# controller_board.net
KiCad netlist of a schematic drawn in EAGLE
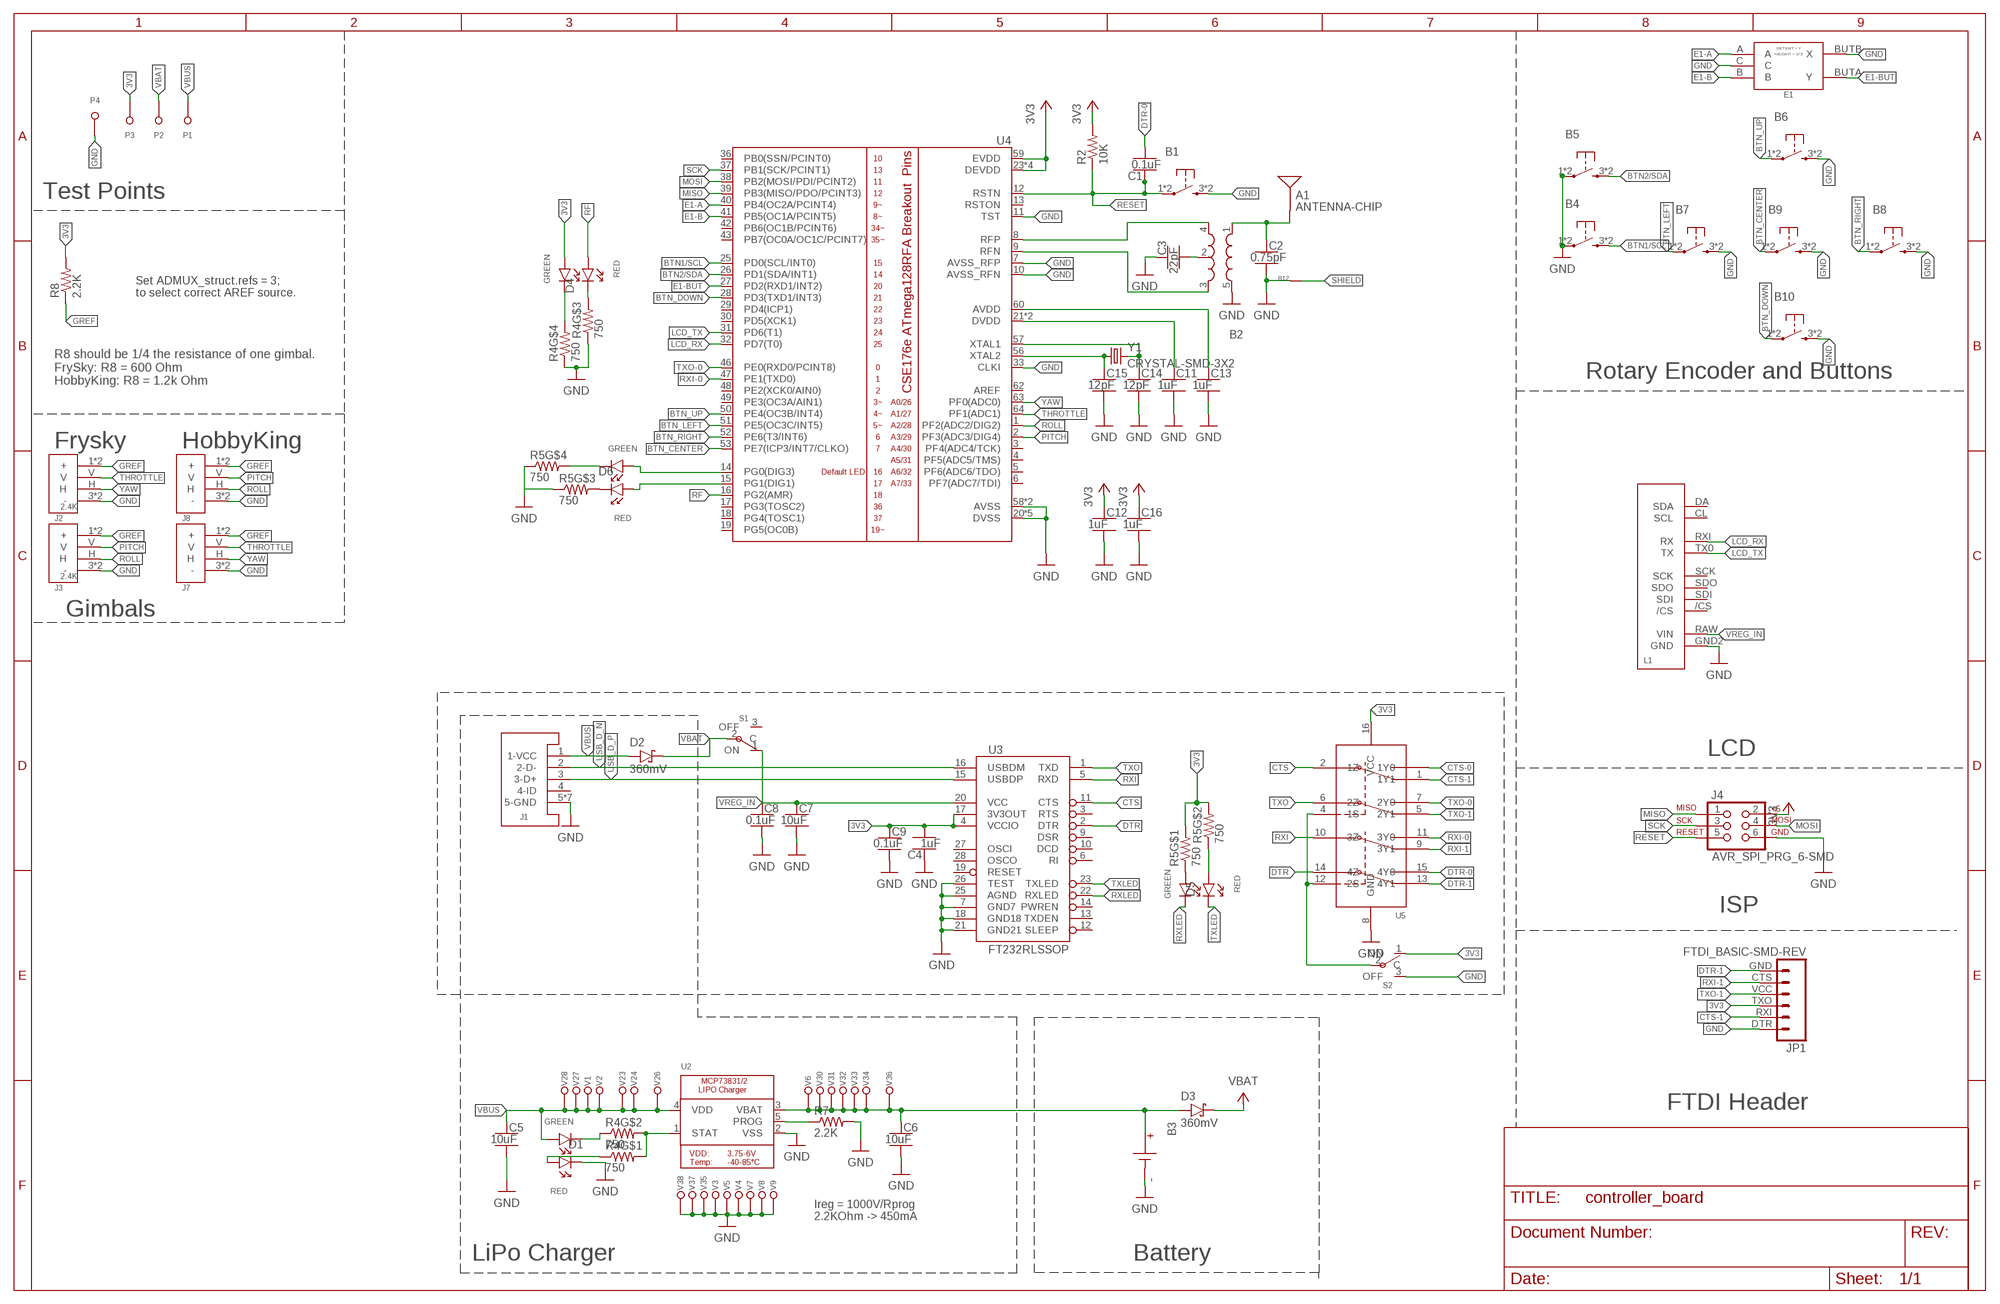
[diagram p0: schematic, sheet 1]

(export (version "E")
  (design (tool "Eeschema 10.0.6"))
  (components
    (comp (ref "A1")
      (value "ANTENNA-CHIP")
      (footprint "eagle-import:ANTENNA-CHIP")
      (fields
        (field (name "MFR") "Linx Technologies Inc.")
        (field (name "MPN") "ANT-2.45-CHP-T")
        (field (name "CREATOR") "Swanson")
        (field (name "REVIEWER") "Swanson")
      )
      (libsource (lib "eagle-import") (part "ANTENNA-CHIP"))
    )
    (comp (ref "B1")
      (value "PUSHBUTTON_-4.5X4.5")
      (footprint "eagle-import:4.5MM_TACTILE_SWITCH_TL3305AF160QG")
      (fields (field (name "CREATOR") "Swanson"))
      (libsource (lib "eagle-import") (part "PUSHBUTTON_-4.5X4.5"))
    )
    (comp (ref "B2")
      (value "BALUN0805")
      (footprint "eagle-import:BALUN")
      (fields
        (field (name "MFR") "Wurth Electronics Inc")
        (field (name "MPN") "748421245")
        (field (name "CREATOR") "Swanson")
        (field (name "REVIEWER") "Swanson")
      )
      (libsource (lib "eagle-import") (part "BALUN0805"))
    )
    (comp (ref "B3")
      (value "BATTERY")
      (footprint "eagle-import:BATTERY-TERMINALS")
      (fields (field (name "CREATOR") "Swanson"))
      (libsource (lib "eagle-import") (part "BATTERY"))
    )
    (comp (ref "B4")
      (value "PUSHBUTTON_-4.5X4.5")
      (footprint "eagle-import:4.5MM_TACTILE_SWITCH_TL3305AF160QG")
      (fields (field (name "CREATOR") "Swanson"))
      (libsource (lib "eagle-import") (part "PUSHBUTTON_-4.5X4.5"))
    )
    (comp (ref "B5")
      (value "PUSHBUTTON_-4.5X4.5")
      (footprint "eagle-import:4.5MM_TACTILE_SWITCH_TL3305AF160QG")
      (fields (field (name "CREATOR") "Swanson"))
      (libsource (lib "eagle-import") (part "PUSHBUTTON_-4.5X4.5"))
    )
    (comp (ref "B6")
      (value "PUSHBUTTON_-4.5X4.5")
      (footprint "eagle-import:4.5MM_TACTILE_SWITCH_TL3305AF160QG")
      (fields (field (name "CREATOR") "Swanson"))
      (libsource (lib "eagle-import") (part "PUSHBUTTON_-4.5X4.5"))
    )
    (comp (ref "B7")
      (value "PUSHBUTTON_-4.5X4.5")
      (footprint "eagle-import:4.5MM_TACTILE_SWITCH_TL3305AF160QG")
      (fields (field (name "CREATOR") "Swanson"))
      (libsource (lib "eagle-import") (part "PUSHBUTTON_-4.5X4.5"))
    )
    (comp (ref "B8")
      (value "PUSHBUTTON_-4.5X4.5")
      (footprint "eagle-import:4.5MM_TACTILE_SWITCH_TL3305AF160QG")
      (fields (field (name "CREATOR") "Swanson"))
      (libsource (lib "eagle-import") (part "PUSHBUTTON_-4.5X4.5"))
    )
    (comp (ref "B9")
      (value "PUSHBUTTON_-4.5X4.5")
      (footprint "eagle-import:4.5MM_TACTILE_SWITCH_TL3305AF160QG")
      (fields (field (name "CREATOR") "Swanson"))
      (libsource (lib "eagle-import") (part "PUSHBUTTON_-4.5X4.5"))
    )
    (comp (ref "B10")
      (value "PUSHBUTTON_-4.5X4.5")
      (footprint "eagle-import:4.5MM_TACTILE_SWITCH_TL3305AF160QG")
      (fields (field (name "CREATOR") "Swanson"))
      (libsource (lib "eagle-import") (part "PUSHBUTTON_-4.5X4.5"))
    )
    (comp (ref "B12")
      (value "NET_BRIDGE")
      (footprint "eagle-import:NET_BRIDGE")
      (fields (field (name "CREATOR") "Michael Gonzalez"))
      (libsource (lib "eagle-import") (part "NET_BRIDGE"))
    )
    (comp (ref "C1")
      (value "0.1uF")
      (footprint "eagle-import:CAPC1608X100")
      (fields (field (name "CREATOR") "Swanson"))
      (libsource (lib "eagle-import") (part "CAPACITOR-NP_SMD-0603_CERAMIC-0.1UF"))
    )
    (comp (ref "C2")
      (value "0.75pF")
      (footprint "eagle-import:CAPC1608X100")
      (fields (field (name "CREATOR") "Swanson"))
      (libsource (lib "eagle-import") (part "CAPACITOR-NP_SMD-0603_CERAMIC-0.75PF"))
    )
    (comp (ref "C3")
      (value "22pF")
      (footprint "eagle-import:CAPC1608X100")
      (fields (field (name "CREATOR") "Swanson"))
      (libsource (lib "eagle-import") (part "CAPACITOR-NP_SMD-0603_CERAMIC-22PF"))
    )
    (comp (ref "C4")
      (value "1uF")
      (footprint "eagle-import:CAPC1608X100")
      (fields (field (name "CREATOR") "Swanson"))
      (libsource (lib "eagle-import") (part "CAPACITOR-NP_SMD-0603_CERAMIC-1UF"))
    )
    (comp (ref "C5")
      (value "10uF")
      (footprint "eagle-import:CAPC1608X100")
      (fields (field (name "CREATOR") "Swanson"))
      (libsource (lib "eagle-import") (part "CAPACITOR-NP_SMD-0603_CERAMIC-10UF"))
    )
    (comp (ref "C6")
      (value "10uF")
      (footprint "eagle-import:CAPC1608X100")
      (fields (field (name "CREATOR") "Swanson"))
      (libsource (lib "eagle-import") (part "CAPACITOR-NP_SMD-0603_CERAMIC-10UF"))
    )
    (comp (ref "C7")
      (value "10uF")
      (footprint "eagle-import:CAPC1608X100")
      (fields (field (name "CREATOR") "Swanson"))
      (libsource (lib "eagle-import") (part "CAPACITOR-NP_SMD-0603_CERAMIC-10UF"))
    )
    (comp (ref "C8")
      (value "0.1uF")
      (footprint "eagle-import:CAPC1608X100")
      (fields (field (name "CREATOR") "Swanson"))
      (libsource (lib "eagle-import") (part "CAPACITOR-NP_SMD-0603_CERAMIC-0.1UF"))
    )
    (comp (ref "C9")
      (value "0.1uF")
      (footprint "eagle-import:CAPC1608X100")
      (fields (field (name "CREATOR") "Swanson"))
      (libsource (lib "eagle-import") (part "CAPACITOR-NP_SMD-0603_CERAMIC-0.1UF"))
    )
    (comp (ref "C11")
      (value "1uF")
      (footprint "eagle-import:CAPC1608X100")
      (fields (field (name "CREATOR") "Swanson"))
      (libsource (lib "eagle-import") (part "CAPACITOR-NP_SMD-0603_CERAMIC-1UF"))
    )
    (comp (ref "C12")
      (value "1uF")
      (footprint "eagle-import:CAPC1608X100")
      (fields (field (name "CREATOR") "Swanson"))
      (libsource (lib "eagle-import") (part "CAPACITOR-NP_SMD-0603_CERAMIC-1UF"))
    )
    (comp (ref "C13")
      (value "1uF")
      (footprint "eagle-import:CAPC1608X100")
      (fields (field (name "CREATOR") "Swanson"))
      (libsource (lib "eagle-import") (part "CAPACITOR-NP_SMD-0603_CERAMIC-1UF"))
    )
    (comp (ref "C14")
      (value "12pF")
      (footprint "eagle-import:CAPC1608X100")
      (fields (field (name "CREATOR") "Swanson"))
      (libsource (lib "eagle-import") (part "CAPACITOR-NP_SMD-0603_CERAMIC-12PF"))
    )
    (comp (ref "C15")
      (value "12pF")
      (footprint "eagle-import:CAPC1608X100")
      (fields (field (name "CREATOR") "Swanson"))
      (libsource (lib "eagle-import") (part "CAPACITOR-NP_SMD-0603_CERAMIC-12PF"))
    )
    (comp (ref "C16")
      (value "1uF")
      (footprint "eagle-import:CAPC1608X100")
      (fields (field (name "CREATOR") "Swanson"))
      (libsource (lib "eagle-import") (part "CAPACITOR-NP_SMD-0603_CERAMIC-1UF"))
    )
    (comp (ref "D1")
      (value "LED-2X-GREEN/RED-1.6X1.5MM")
      (footprint "eagle-import:LED-2X-LITE-ON-1.6MMX1.5MM")
      (fields
        (field (name "COLOR2") "RED")
        (field (name "COLOR1") "GREEN")
        (field (name "CREATOR") "Swanson")
      )
      (libsource (lib "eagle-import") (part "LED-2X-GREEN/RED-1.6X1.5MM"))
    )
    (comp (ref "D2")
      (value "360mV")
      (footprint "eagle-import:SOD3716X135_HS")
      (fields
        (field (name "MFR") "Toshiba Semiconductor and Storage")
        (field (name "MPN") "CRS08(TE85L,Q,M)")
        (field (name "CREATOR") "Swanson")
        (field (name "REVIEWER") "Swanson")
      )
      (libsource (lib "eagle-import") (part "DIODE-SCHOTTKY_SMD-SOD123-360MV"))
    )
    (comp (ref "D3")
      (value "360mV")
      (footprint "eagle-import:SOD3716X135_HS")
      (fields
        (field (name "MFR") "Toshiba Semiconductor and Storage")
        (field (name "MPN") "CRS08(TE85L,Q,M)")
        (field (name "CREATOR") "Swanson")
        (field (name "REVIEWER") "Swanson")
      )
      (libsource (lib "eagle-import") (part "DIODE-SCHOTTKY_SMD-SOD123-360MV"))
    )
    (comp (ref "D4")
      (value "LED-2X-GREEN/RED-1.6X1.5MM")
      (footprint "eagle-import:LED-2X-LITE-ON-1.6MMX1.5MM")
      (fields
        (field (name "COLOR2") "RED")
        (field (name "COLOR1") "GREEN")
        (field (name "CREATOR") "Swanson")
      )
      (libsource (lib "eagle-import") (part "LED-2X-GREEN/RED-1.6X1.5MM"))
    )
    (comp (ref "D5")
      (value "LED-2X-GREEN/RED-1.6X1.5MM")
      (footprint "eagle-import:LED-2X-LITE-ON-1.6MMX1.5MM")
      (fields
        (field (name "COLOR2") "RED")
        (field (name "COLOR1") "GREEN")
        (field (name "CREATOR") "Swanson")
      )
      (libsource (lib "eagle-import") (part "LED-2X-GREEN/RED-1.6X1.5MM"))
    )
    (comp (ref "D6")
      (value "LED-2X-GREEN/RED-1.6X1.5MM")
      (footprint "eagle-import:LED-2X-LITE-ON-1.6MMX1.5MM")
      (fields
        (field (name "COLOR2") "RED")
        (field (name "COLOR1") "GREEN")
        (field (name "CREATOR") "Swanson")
      )
      (libsource (lib "eagle-import") (part "LED-2X-GREEN/RED-1.6X1.5MM"))
    )
    (comp (ref "E1")
      (value "ROTARY-ENCODER-W/BUTTON-BOURNS-PEC12R-4217F")
      (footprint "eagle-import:BOURNS-PEC12R")
      (fields (field (name "DETENT") "Y") (field (name "HEIGHT") "17.5") (field (name "CREATOR") "Swanson"))
      (libsource (lib "eagle-import") (part "ROTARY-ENCODER-W/BUTTON-BOURNS-PEC12R-4217F"))
    )
    (comp (ref "J1")
      (value "USB-MICROA-AMPHENOL-10118192-0001LF")
      (footprint "eagle-import:USB-MICROA-10118192-0001LF")
      (fields (field (name "CREATOR") "Swanson"))
      (libsource (lib "eagle-import") (part "USB-MICROA-AMPHENOL-10118192-0001LF"))
    )
    (comp (ref "J2")
      (value "2.4K")
      (footprint "eagle-import:JST-13-PTH")
      (fields (field (name "CREATOR") "Swanson"))
      (libsource (lib "eagle-import") (part "FRSKY-GIMBAL-FRYSKY"))
    )
    (comp (ref "J3")
      (value "2.4K")
      (footprint "eagle-import:JST-13-PTH")
      (fields (field (name "SPICEPREFIX") "E") (field (name "CREATOR") "Swanson"))
      (libsource (lib "eagle-import") (part "FRSKY-GIMBAL-FRYSKY"))
    )
    (comp (ref "J4")
      (value "AVR_SPI_PRG_6-SMD")
      (footprint "eagle-import:2X3-SMD")
      (fields (field (name "CREATOR") "Swanson"))
      (libsource (lib "eagle-import") (part "AVR_SPI_PRG_6-SMD"))
    )
    (comp (ref "J7")
      (value "FRSKY-GIMBAL-2X-SERVO-SMD")
      (footprint "eagle-import:2X-SERVO-SMD")
      (libsource (lib "eagle-import") (part "FRSKY-GIMBAL-2X-SERVO-SMD"))
    )
    (comp (ref "J8")
      (value "FRSKY-GIMBAL-2X-SERVO-SMD")
      (footprint "eagle-import:2X-SERVO-SMD")
      (libsource (lib "eagle-import") (part "FRSKY-GIMBAL-2X-SERVO-SMD"))
    )
    (comp (ref "JP1")
      (value "FTDI_BASIC-SMD-REV")
      (footprint "eagle-import:FTDI-BASIC-SMD")
      (libsource (lib "eagle-import") (part "FTDI_BASIC-SMD-REV"))
    )
    (comp (ref "L1")
      (value "SPARKFUN_SERLCD_SERIAL_REDUCED-SMD")
      (footprint "eagle-import:SPARKFUN_SERLCD_16X2_REDUCED_SMD")
      (fields (field (name "CREATOR") "Swanson"))
      (libsource (lib "eagle-import") (part "SPARKFUN_SERLCD_SERIAL_REDUCED-SMD"))
    )
    (comp (ref "P1")
      (value "TEST-POINT")
      (footprint "eagle-import:TEST-POINT-KEYSTONE-5000")
      (fields (field (name "CREATOR") "Swanson"))
      (libsource (lib "eagle-import") (part "TEST-POINT"))
    )
    (comp (ref "P2")
      (value "TEST-POINT")
      (footprint "eagle-import:TEST-POINT-KEYSTONE-5000")
      (fields (field (name "CREATOR") "Swanson"))
      (libsource (lib "eagle-import") (part "TEST-POINT"))
    )
    (comp (ref "P3")
      (value "TEST-POINT")
      (footprint "eagle-import:TEST-POINT-KEYSTONE-5000")
      (fields (field (name "CREATOR") "Swanson"))
      (libsource (lib "eagle-import") (part "TEST-POINT"))
    )
    (comp (ref "P4")
      (value "TEST-POINT")
      (footprint "eagle-import:TEST-POINT-KEYSTONE-5000")
      (fields (field (name "CREATOR") "Swanson"))
      (libsource (lib "eagle-import") (part "TEST-POINT"))
    )
    (comp (ref "R2")
      (value "10K")
      (footprint "eagle-import:RESC1608X55")
      (fields (field (name "CREATOR") "Swanson"))
      (libsource (lib "eagle-import") (part "RESISTOR_SMD-0603-10K"))
    )
    (comp (ref "R4")
      (value "750")
      (footprint "eagle-import:RESCAXS50P200X100X45-8")
      (fields (field (name "CREATOR") "Swanson"))
      (libsource (lib "eagle-import") (part "RESISTOR-PACK-4X-750"))
    )
    (comp (ref "R5")
      (value "750")
      (footprint "eagle-import:RESCAXS50P200X100X45-8")
      (fields (field (name "CREATOR") "Swanson"))
      (libsource (lib "eagle-import") (part "RESISTOR-PACK-4X-750"))
    )
    (comp (ref "R7")
      (value "2.2K")
      (footprint "eagle-import:RESC1608X55")
      (fields (field (name "CREATOR") "Swanson"))
      (libsource (lib "eagle-import") (part "RESISTOR_SMD-0603-2.2K"))
    )
    (comp (ref "R8")
      (value "2.2K")
      (footprint "eagle-import:RESC1608X55")
      (fields (field (name "CREATOR") "Swanson"))
      (libsource (lib "eagle-import") (part "RESISTOR_SMD-0603-2.2K"))
    )
    (comp (ref "S1")
      (value "POWER-SWITCH-MFS201N-9-Z-SMD-VERTICAL")
      (footprint "eagle-import:JS102011JCQN")
      (fields (field (name "CREATOR") "Swanson"))
      (libsource (lib "eagle-import") (part "POWER-SWITCH-MFS201N-9-Z-SMD-VERTICAL"))
    )
    (comp (ref "S2")
      (value "POWER-SWITCH-MFS201N-9-Z-SMD-VERTICAL")
      (footprint "eagle-import:JS102011JCQN")
      (fields (field (name "CREATOR") "Swanson"))
      (libsource (lib "eagle-import") (part "POWER-SWITCH-MFS201N-9-Z-SMD-VERTICAL"))
    )
    (comp (ref "U2")
      (value "MCP73831T-2ACI/OT")
      (footprint "eagle-import:SOT23-5")
      (fields (field (name "CREATOR") "Adafruit"))
      (libsource (lib "eagle-import") (part "MCP73831/2"))
    )
    (comp (ref "U3")
      (value "FT232RLSSOP")
      (footprint "eagle-import:SSOP28DB")
      (fields (field (name "CREATOR") "Swanson"))
      (libsource (lib "eagle-import") (part "FT232RLSSOP"))
    )
    (comp (ref "U4")
      (value "ATMEGA128RFA1")
      (footprint "eagle-import:QFN-64")
      (fields
        (field (name "MFR") "Atmel")
        (field (name "MPN") "ATMEGA128RFA1-ZUR00")
        (field (name "CREATOR") "Swanson")
        (field (name "REVIEWER") "Swanson")
      )
      (libsource (lib "eagle-import") (part "ATMEGA128RFA1"))
    )
    (comp (ref "U5")
      (value "DPDT-X2")
      (footprint "eagle-import:SOP65P640X110-16")
      (fields (field (name "CREATOR") "Swanson"))
      (libsource (lib "eagle-import") (part "DPDT-X2"))
    )
    (comp (ref "V1")
      (value "LOCKED-VIA-0.2")
      (footprint "eagle-import:VIA-0.2MM")
      (fields (field (name "CREATOR") "Swanson"))
      (libsource (lib "eagle-import") (part "LOCKED-VIA-0.2"))
    )
    (comp (ref "V2")
      (value "LOCKED-VIA-0.2")
      (footprint "eagle-import:VIA-0.2MM")
      (fields (field (name "CREATOR") "Swanson"))
      (libsource (lib "eagle-import") (part "LOCKED-VIA-0.2"))
    )
    (comp (ref "V3")
      (value "LOCKED-VIA-0.2")
      (footprint "eagle-import:VIA-0.2MM")
      (fields (field (name "CREATOR") "Swanson"))
      (libsource (lib "eagle-import") (part "LOCKED-VIA-0.2"))
    )
    (comp (ref "V4")
      (value "LOCKED-VIA-0.2")
      (footprint "eagle-import:VIA-0.2MM")
      (fields (field (name "CREATOR") "Swanson"))
      (libsource (lib "eagle-import") (part "LOCKED-VIA-0.2"))
    )
    (comp (ref "V5")
      (value "LOCKED-VIA-0.2")
      (footprint "eagle-import:VIA-0.2MM")
      (fields (field (name "CREATOR") "Swanson"))
      (libsource (lib "eagle-import") (part "LOCKED-VIA-0.2"))
    )
    (comp (ref "V6")
      (value "LOCKED-VIA-0.2")
      (footprint "eagle-import:VIA-0.2MM")
      (fields (field (name "CREATOR") "Swanson"))
      (libsource (lib "eagle-import") (part "LOCKED-VIA-0.2"))
    )
    (comp (ref "V7")
      (value "LOCKED-VIA-0.2")
      (footprint "eagle-import:VIA-0.2MM")
      (fields (field (name "CREATOR") "Swanson"))
      (libsource (lib "eagle-import") (part "LOCKED-VIA-0.2"))
    )
    (comp (ref "V8")
      (value "LOCKED-VIA-0.2")
      (footprint "eagle-import:VIA-0.2MM")
      (fields (field (name "CREATOR") "Swanson"))
      (libsource (lib "eagle-import") (part "LOCKED-VIA-0.2"))
    )
    (comp (ref "V9")
      (value "LOCKED-VIA-0.2")
      (footprint "eagle-import:VIA-0.2MM")
      (fields (field (name "CREATOR") "Swanson"))
      (libsource (lib "eagle-import") (part "LOCKED-VIA-0.2"))
    )
    (comp (ref "V23")
      (value "LOCKED-VIA-0.2")
      (footprint "eagle-import:VIA-0.2MM")
      (fields (field (name "CREATOR") "Swanson"))
      (libsource (lib "eagle-import") (part "LOCKED-VIA-0.2"))
    )
    (comp (ref "V24")
      (value "LOCKED-VIA-0.2")
      (footprint "eagle-import:VIA-0.2MM")
      (fields (field (name "CREATOR") "Swanson"))
      (libsource (lib "eagle-import") (part "LOCKED-VIA-0.2"))
    )
    (comp (ref "V26")
      (value "LOCKED-VIA-0.2")
      (footprint "eagle-import:VIA-0.2MM")
      (fields (field (name "CREATOR") "Swanson"))
      (libsource (lib "eagle-import") (part "LOCKED-VIA-0.2"))
    )
    (comp (ref "V27")
      (value "LOCKED-VIA-0.2")
      (footprint "eagle-import:VIA-0.2MM")
      (fields (field (name "CREATOR") "Swanson"))
      (libsource (lib "eagle-import") (part "LOCKED-VIA-0.2"))
    )
    (comp (ref "V28")
      (value "LOCKED-VIA-0.2")
      (footprint "eagle-import:VIA-0.2MM")
      (fields (field (name "CREATOR") "Swanson"))
      (libsource (lib "eagle-import") (part "LOCKED-VIA-0.2"))
    )
    (comp (ref "V30")
      (value "LOCKED-VIA-0.2")
      (footprint "eagle-import:VIA-0.2MM")
      (fields (field (name "CREATOR") "Swanson"))
      (libsource (lib "eagle-import") (part "LOCKED-VIA-0.2"))
    )
    (comp (ref "V31")
      (value "LOCKED-VIA-0.2")
      (footprint "eagle-import:VIA-0.2MM")
      (fields (field (name "CREATOR") "Swanson"))
      (libsource (lib "eagle-import") (part "LOCKED-VIA-0.2"))
    )
    (comp (ref "V32")
      (value "LOCKED-VIA-0.2")
      (footprint "eagle-import:VIA-0.2MM")
      (fields (field (name "CREATOR") "Swanson"))
      (libsource (lib "eagle-import") (part "LOCKED-VIA-0.2"))
    )
    (comp (ref "V33")
      (value "LOCKED-VIA-0.2")
      (footprint "eagle-import:VIA-0.2MM")
      (fields (field (name "CREATOR") "Swanson"))
      (libsource (lib "eagle-import") (part "LOCKED-VIA-0.2"))
    )
    (comp (ref "V34")
      (value "LOCKED-VIA-0.2")
      (footprint "eagle-import:VIA-0.2MM")
      (fields (field (name "CREATOR") "Swanson"))
      (libsource (lib "eagle-import") (part "LOCKED-VIA-0.2"))
    )
    (comp (ref "V35")
      (value "LOCKED-VIA-0.2")
      (footprint "eagle-import:VIA-0.2MM")
      (fields (field (name "CREATOR") "Swanson"))
      (libsource (lib "eagle-import") (part "LOCKED-VIA-0.2"))
    )
    (comp (ref "V36")
      (value "LOCKED-VIA-0.2")
      (footprint "eagle-import:VIA-0.2MM")
      (fields (field (name "CREATOR") "Swanson"))
      (libsource (lib "eagle-import") (part "LOCKED-VIA-0.2"))
    )
    (comp (ref "V37")
      (value "LOCKED-VIA-0.2")
      (footprint "eagle-import:VIA-0.2MM")
      (fields (field (name "CREATOR") "Swanson"))
      (libsource (lib "eagle-import") (part "LOCKED-VIA-0.2"))
    )
    (comp (ref "V38")
      (value "LOCKED-VIA-0.2")
      (footprint "eagle-import:VIA-0.2MM")
      (fields (field (name "CREATOR") "Swanson"))
      (libsource (lib "eagle-import") (part "LOCKED-VIA-0.2"))
    )
    (comp (ref "Y1")
      (value "CRYSTAL-SMD-3X2")
      (footprint "eagle-import:OSCCC320X250X85")
      (fields (field (name "CREATOR") "Swanson"))
      (libsource (lib "eagle-import") (part "CRYSTAL-SMD-3X2"))
    )
  )
  (nets
    (net (code "1") (name "3V3") (class "Default")
      (node (ref "C12") (pin "1") (pinfunction "1_1") (pintype "passive"))
      (node (ref "C16") (pin "1") (pinfunction "1_1") (pintype "passive"))
      (node (ref "C4") (pin "2") (pinfunction "2_2") (pintype "passive"))
      (node (ref "C9") (pin "1") (pinfunction "1_1") (pintype "passive"))
      (node (ref "D4") (pin "A2") (pinfunction "A2_A2") (pintype "passive"))
      (node (ref "J4") (pin "2") (pinfunction "2_2") (pintype "passive"))
      (node (ref "JP1") (pin "TXO") (pinfunction "4_TXO") (pintype "passive"))
      (node (ref "P3") (pin "T") (pinfunction "T_T") (pintype "bidirectional"))
      (node (ref "R2") (pin "2") (pinfunction "2_2") (pintype "passive"))
      (node (ref "R5") (pin "5") (pinfunction "2_5") (pintype "passive"))
      (node (ref "R5") (pin "6") (pinfunction "2_6") (pintype "passive"))
      (node (ref "R8") (pin "2") (pinfunction "2_2") (pintype "passive"))
      (node (ref "S2") (pin "1") (pinfunction "ON_1") (pintype "bidirectional"))
      (node (ref "U3") (pin "17") (pinfunction "3V3OUT_17") (pintype "output"))
      (node (ref "U3") (pin "4") (pinfunction "VCCIO_4") (pintype "power_in"))
      (node (ref "U4") (pin "23") (pinfunction "DEVDD_23") (pintype "bidirectional"))
      (node (ref "U4") (pin "34") (pinfunction "DEVDD_34") (pintype "bidirectional"))
      (node (ref "U4") (pin "44") (pinfunction "DEVDD_44") (pintype "bidirectional"))
      (node (ref "U4") (pin "54") (pinfunction "DEVDD_54") (pintype "bidirectional"))
      (node (ref "U4") (pin "59") (pinfunction "EVDD_59") (pintype "bidirectional"))
      (node (ref "U5") (pin "16") (pinfunction "VCC_16") (pintype "bidirectional"))
    )
    (net (code "2") (name "BTN1{slash}SCL") (class "Default")
      (node (ref "B4") (pin "3") (pinfunction "2_3") (pintype "passive"))
      (node (ref "B4") (pin "4") (pinfunction "2_4") (pintype "passive"))
      (node (ref "U4") (pin "25") (pinfunction "PD0(SCL/INT0)_25") (pintype "bidirectional"))
    )
    (net (code "3") (name "BTN2{slash}SDA") (class "Default")
      (node (ref "B5") (pin "3") (pinfunction "2_3") (pintype "passive"))
      (node (ref "B5") (pin "4") (pinfunction "2_4") (pintype "passive"))
      (node (ref "U4") (pin "26") (pinfunction "PD1(SDA/INT1)_26") (pintype "bidirectional"))
    )
    (net (code "4") (name "BTN_CENTER") (class "Default")
      (node (ref "B9") (pin "1") (pinfunction "1_1") (pintype "passive"))
      (node (ref "B9") (pin "2") (pinfunction "1_2") (pintype "passive"))
      (node (ref "U4") (pin "53") (pinfunction "PE7(ICP3/INT7/CLKO)_53") (pintype "bidirectional"))
    )
    (net (code "5") (name "BTN_DOWN") (class "Default")
      (node (ref "B10") (pin "1") (pinfunction "1_1") (pintype "passive"))
      (node (ref "B10") (pin "2") (pinfunction "1_2") (pintype "passive"))
      (node (ref "U4") (pin "28") (pinfunction "PD3(TXD1/INT3)_28") (pintype "bidirectional"))
    )
    (net (code "6") (name "BTN_LEFT") (class "Default")
      (node (ref "B7") (pin "1") (pinfunction "1_1") (pintype "passive"))
      (node (ref "B7") (pin "2") (pinfunction "1_2") (pintype "passive"))
      (node (ref "U4") (pin "51") (pinfunction "PE5(OC3C/INT5)_51") (pintype "bidirectional"))
    )
    (net (code "7") (name "BTN_RIGHT") (class "Default")
      (node (ref "B8") (pin "1") (pinfunction "1_1") (pintype "passive"))
      (node (ref "B8") (pin "2") (pinfunction "1_2") (pintype "passive"))
      (node (ref "U4") (pin "52") (pinfunction "PE6(T3/INT6)_52") (pintype "bidirectional"))
    )
    (net (code "8") (name "BTN_UP") (class "Default")
      (node (ref "B6") (pin "1") (pinfunction "1_1") (pintype "passive"))
      (node (ref "B6") (pin "2") (pinfunction "1_2") (pintype "passive"))
      (node (ref "U4") (pin "50") (pinfunction "PE4(OC3B/INT4)_50") (pintype "bidirectional"))
    )
    (net (code "9") (name "CTS") (class "Default")
      (node (ref "U3") (pin "11") (pinfunction "CTS_11") (pintype "input"))
      (node (ref "U5") (pin "2") (pinfunction "1Z_2") (pintype "bidirectional"))
    )
    (net (code "10") (name "CTS-0") (class "Default")
      (node (ref "U5") (pin "3") (pinfunction "1Y0_3") (pintype "bidirectional"))
    )
    (net (code "11") (name "CTS-1") (class "Default")
      (node (ref "JP1") (pin "RXI") (pinfunction "5_RXI") (pintype "passive"))
      (node (ref "U5") (pin "1") (pinfunction "1Y1_1") (pintype "bidirectional"))
    )
    (net (code "12") (name "DTR") (class "Default")
      (node (ref "U3") (pin "2") (pinfunction "DTR_2") (pintype "output"))
      (node (ref "U5") (pin "14") (pinfunction "4Z_14") (pintype "bidirectional"))
    )
    (net (code "13") (name "DTR-0") (class "Default")
      (node (ref "C1") (pin "2") (pinfunction "2_2") (pintype "passive"))
      (node (ref "U5") (pin "15") (pinfunction "4Y0_15") (pintype "bidirectional"))
    )
    (net (code "14") (name "DTR-1") (class "Default")
      (node (ref "JP1") (pin "GND") (pinfunction "1_GND") (pintype "passive"))
      (node (ref "U5") (pin "13") (pinfunction "4Y1_13") (pintype "bidirectional"))
    )
    (net (code "15") (name "E1-A") (class "Default")
      (node (ref "E1") (pin "A") (pinfunction "A_A") (pintype "bidirectional"))
      (node (ref "U4") (pin "40") (pinfunction "PB4(OC2A/PCINT4)_40") (pintype "bidirectional"))
    )
    (net (code "16") (name "E1-B") (class "Default")
      (node (ref "E1") (pin "B") (pinfunction "B_B") (pintype "bidirectional"))
      (node (ref "U4") (pin "41") (pinfunction "PB5(OC1A/PCINT5)_41") (pintype "bidirectional"))
    )
    (net (code "17") (name "E1-BUT") (class "Default")
      (node (ref "E1") (pin "BUTA") (pinfunction "Y_BUTA") (pintype "bidirectional"))
      (node (ref "U4") (pin "27") (pinfunction "PD2(RXD1/INT2)_27") (pintype "bidirectional"))
    )
    (net (code "18") (name "GND") (class "Default")
      (node (ref "B1") (pin "3") (pinfunction "2_3") (pintype "passive"))
      (node (ref "B1") (pin "4") (pinfunction "2_4") (pintype "passive"))
      (node (ref "B10") (pin "3") (pinfunction "2_3") (pintype "passive"))
      (node (ref "B10") (pin "4") (pinfunction "2_4") (pintype "passive"))
      (node (ref "B12") (pin "P1") (pinfunction "P1_P1") (pintype "bidirectional"))
      (node (ref "B2") (pin "5") (pinfunction "GND_5") (pintype "bidirectional"))
      (node (ref "B3") (pin "-") (pinfunction "N_-") (pintype "bidirectional"))
      (node (ref "B4") (pin "1") (pinfunction "1_1") (pintype "passive"))
      (node (ref "B4") (pin "2") (pinfunction "1_2") (pintype "passive"))
      (node (ref "B5") (pin "1") (pinfunction "1_1") (pintype "passive"))
      (node (ref "B5") (pin "2") (pinfunction "1_2") (pintype "passive"))
      (node (ref "B6") (pin "3") (pinfunction "2_3") (pintype "passive"))
      (node (ref "B6") (pin "4") (pinfunction "2_4") (pintype "passive"))
      (node (ref "B7") (pin "3") (pinfunction "2_3") (pintype "passive"))
      (node (ref "B7") (pin "4") (pinfunction "2_4") (pintype "passive"))
      (node (ref "B8") (pin "3") (pinfunction "2_3") (pintype "passive"))
      (node (ref "B8") (pin "4") (pinfunction "2_4") (pintype "passive"))
      (node (ref "B9") (pin "3") (pinfunction "2_3") (pintype "passive"))
      (node (ref "B9") (pin "4") (pinfunction "2_4") (pintype "passive"))
      (node (ref "C11") (pin "2") (pinfunction "2_2") (pintype "passive"))
      (node (ref "C12") (pin "2") (pinfunction "2_2") (pintype "passive"))
      (node (ref "C13") (pin "2") (pinfunction "2_2") (pintype "passive"))
      (node (ref "C14") (pin "2") (pinfunction "2_2") (pintype "passive"))
      (node (ref "C15") (pin "2") (pinfunction "2_2") (pintype "passive"))
      (node (ref "C16") (pin "2") (pinfunction "2_2") (pintype "passive"))
      (node (ref "C2") (pin "2") (pinfunction "2_2") (pintype "passive"))
      (node (ref "C3") (pin "1") (pinfunction "1_1") (pintype "passive"))
      (node (ref "C4") (pin "1") (pinfunction "1_1") (pintype "passive"))
      (node (ref "C5") (pin "2") (pinfunction "2_2") (pintype "passive"))
      (node (ref "C6") (pin "2") (pinfunction "2_2") (pintype "passive"))
      (node (ref "C7") (pin "2") (pinfunction "2_2") (pintype "passive"))
      (node (ref "C8") (pin "2") (pinfunction "2_2") (pintype "passive"))
      (node (ref "C9") (pin "2") (pinfunction "2_2") (pintype "passive"))
      (node (ref "D1") (pin "C1") (pinfunction "C1_C1") (pintype "passive"))
      (node (ref "E1") (pin "BUTB") (pinfunction "X_BUTB") (pintype "bidirectional"))
      (node (ref "E1") (pin "C") (pinfunction "C_C") (pintype "bidirectional"))
      (node (ref "J1") (pin "10") (pinfunction "5-GND_10") (pintype "bidirectional"))
      (node (ref "J1") (pin "11") (pinfunction "5-GND_11") (pintype "bidirectional"))
      (node (ref "J1") (pin "5") (pinfunction "5-GND_5") (pintype "bidirectional"))
      (node (ref "J1") (pin "6") (pinfunction "5-GND_6") (pintype "bidirectional"))
      (node (ref "J1") (pin "7") (pinfunction "5-GND_7") (pintype "bidirectional"))
      (node (ref "J1") (pin "8") (pinfunction "5-GND_8") (pintype "bidirectional"))
      (node (ref "J1") (pin "9") (pinfunction "5-GND_9") (pintype "bidirectional"))
      (node (ref "J2") (pin "3") (pinfunction "-_3") (pintype "bidirectional"))
      (node (ref "J2") (pin "6") (pinfunction "-_6") (pintype "bidirectional"))
      (node (ref "J3") (pin "3") (pinfunction "-_3") (pintype "bidirectional"))
      (node (ref "J3") (pin "6") (pinfunction "-_6") (pintype "bidirectional"))
      (node (ref "J4") (pin "6") (pinfunction "6_6") (pintype "passive"))
      (node (ref "J7") (pin "3") (pinfunction "-_3") (pintype "bidirectional"))
      (node (ref "J7") (pin "6") (pinfunction "-_6") (pintype "bidirectional"))
      (node (ref "J8") (pin "3") (pinfunction "-_3") (pintype "bidirectional"))
      (node (ref "J8") (pin "6") (pinfunction "-_6") (pintype "bidirectional"))
      (node (ref "JP1") (pin "DTR") (pinfunction "6_DTR") (pintype "passive"))
      (node (ref "L1") (pin "GND2") (pinfunction "GND_GND2") (pintype "bidirectional"))
      (node (ref "P4") (pin "T") (pinfunction "T_T") (pintype "bidirectional"))
      (node (ref "R4") (pin "1") (pinfunction "1_1") (pintype "passive"))
      (node (ref "R4") (pin "2") (pinfunction "1_2") (pintype "passive"))
      (node (ref "R5") (pin "1") (pinfunction "1_1") (pintype "passive"))
      (node (ref "R5") (pin "2") (pinfunction "1_2") (pintype "passive"))
      (node (ref "R7") (pin "2") (pinfunction "2_2") (pintype "passive"))
      (node (ref "S2") (pin "3") (pinfunction "OFF_3") (pintype "bidirectional"))
      (node (ref "U2") (pin "2") (pinfunction "VSS_2") (pintype "power_in"))
      (node (ref "U3") (pin "18") (pinfunction "GND18_18") (pintype "power_in"))
      (node (ref "U3") (pin "21") (pinfunction "GND21_21") (pintype "power_in"))
      (node (ref "U3") (pin "25") (pinfunction "AGND_25") (pintype "power_in"))
      (node (ref "U3") (pin "26") (pinfunction "TEST_26") (pintype "input"))
      (node (ref "U3") (pin "7") (pinfunction "GND7_7") (pintype "power_in"))
      (node (ref "U4") (pin "10") (pinfunction "AVSS_RFN_10") (pintype "bidirectional"))
      (node (ref "U4") (pin "11") (pinfunction "TST_11") (pintype "bidirectional"))
      (node (ref "U4") (pin "20") (pinfunction "DVSS_20") (pintype "bidirectional"))
      (node (ref "U4") (pin "24") (pinfunction "DVSS_24") (pintype "bidirectional"))
      (node (ref "U4") (pin "33") (pinfunction "CLKI_33") (pintype "bidirectional"))
      (node (ref "U4") (pin "35") (pinfunction "DVSS_35") (pintype "bidirectional"))
      (node (ref "U4") (pin "45") (pinfunction "DVSS_45") (pintype "bidirectional"))
      (node (ref "U4") (pin "55") (pinfunction "DVSS_55") (pintype "bidirectional"))
      (node (ref "U4") (pin "58") (pinfunction "AVSS_58") (pintype "bidirectional"))
      (node (ref "U4") (pin "61") (pinfunction "AVSS_61") (pintype "bidirectional"))
      (node (ref "U4") (pin "7") (pinfunction "AVSS_RFP_7") (pintype "bidirectional"))
      (node (ref "U5") (pin "8") (pinfunction "GND_8") (pintype "bidirectional"))
      (node (ref "V3") (pin "P1") (pinfunction "N_P1") (pintype "bidirectional"))
      (node (ref "V35") (pin "P1") (pinfunction "N_P1") (pintype "bidirectional"))
      (node (ref "V37") (pin "P1") (pinfunction "N_P1") (pintype "bidirectional"))
      (node (ref "V38") (pin "P1") (pinfunction "N_P1") (pintype "bidirectional"))
      (node (ref "V4") (pin "P1") (pinfunction "N_P1") (pintype "bidirectional"))
      (node (ref "V5") (pin "P1") (pinfunction "N_P1") (pintype "bidirectional"))
      (node (ref "V7") (pin "P1") (pinfunction "N_P1") (pintype "bidirectional"))
      (node (ref "V8") (pin "P1") (pinfunction "N_P1") (pintype "bidirectional"))
      (node (ref "V9") (pin "P1") (pinfunction "N_P1") (pintype "bidirectional"))
    )
    (net (code "19") (name "GREF") (class "Default")
      (node (ref "J2") (pin "1") (pinfunction "+_1") (pintype "bidirectional"))
      (node (ref "J2") (pin "4") (pinfunction "+_4") (pintype "bidirectional"))
      (node (ref "J3") (pin "1") (pinfunction "+_1") (pintype "bidirectional"))
      (node (ref "J3") (pin "4") (pinfunction "+_4") (pintype "bidirectional"))
      (node (ref "J7") (pin "1") (pinfunction "+_1") (pintype "bidirectional"))
      (node (ref "J7") (pin "4") (pinfunction "+_4") (pintype "bidirectional"))
      (node (ref "J8") (pin "1") (pinfunction "+_1") (pintype "bidirectional"))
      (node (ref "J8") (pin "4") (pinfunction "+_4") (pintype "bidirectional"))
      (node (ref "R8") (pin "1") (pinfunction "1_1") (pintype "passive"))
    )
    (net (code "20") (name "LCD_RX") (class "Default")
      (node (ref "L1") (pin "RXI") (pinfunction "RX_RXI") (pintype "bidirectional"))
      (node (ref "U4") (pin "32") (pinfunction "PD7(T0)_32") (pintype "bidirectional"))
    )
    (net (code "21") (name "LCD_TX") (class "Default")
      (node (ref "L1") (pin "TX0") (pinfunction "TX_TX0") (pintype "bidirectional"))
      (node (ref "U4") (pin "31") (pinfunction "PD6(T1)_31") (pintype "bidirectional"))
    )
    (net (code "22") (name "MISO") (class "Default")
      (node (ref "J4") (pin "1") (pinfunction "1_1") (pintype "passive"))
      (node (ref "U4") (pin "39") (pinfunction "PB3(MISO/PDO/PCINT3)_39") (pintype "bidirectional"))
    )
    (net (code "23") (name "MOSI") (class "Default")
      (node (ref "J4") (pin "4") (pinfunction "4_4") (pintype "passive"))
      (node (ref "U4") (pin "38") (pinfunction "PB2(MOSI/PDI/PCINT2)_38") (pintype "bidirectional"))
    )
    (net (code "24") (name "Net-(A1-SIGNAL)") (class "Default")
      (node (ref "A1") (pin "FEED") (pinfunction "SIGNAL_FEED") (pintype "bidirectional"))
      (node (ref "B2") (pin "1") (pinfunction "IN_1") (pintype "bidirectional"))
      (node (ref "C2") (pin "1") (pinfunction "1_1") (pintype "passive"))
    )
    (net (code "25") (name "Net-(B2-GND-Pad2)") (class "Default")
      (node (ref "B2") (pin "2") (pinfunction "GND_2") (pintype "bidirectional"))
      (node (ref "C3") (pin "2") (pinfunction "2_2") (pintype "passive"))
    )
    (net (code "26") (name "Net-(B2-OUT1)") (class "Default")
      (node (ref "B2") (pin "4") (pinfunction "OUT1_4") (pintype "bidirectional"))
      (node (ref "U4") (pin "8") (pinfunction "RFP_8") (pintype "bidirectional"))
    )
    (net (code "27") (name "Net-(B2-OUT2)") (class "Default")
      (node (ref "B2") (pin "3") (pinfunction "OUT2_3") (pintype "bidirectional"))
      (node (ref "U4") (pin "9") (pinfunction "RFN_9") (pintype "bidirectional"))
    )
    (net (code "28") (name "Net-(B3-P)") (class "Default")
      (node (ref "B3") (pin "+") (pinfunction "P_+") (pintype "bidirectional"))
      (node (ref "C6") (pin "1") (pinfunction "1_1") (pintype "passive"))
      (node (ref "D3") (pin "A") (pinfunction "A_A") (pintype "passive"))
      (node (ref "U2") (pin "3") (pinfunction "VBAT_3") (pintype "power_in"))
      (node (ref "V30") (pin "P1") (pinfunction "N_P1") (pintype "bidirectional"))
      (node (ref "V31") (pin "P1") (pinfunction "N_P1") (pintype "bidirectional"))
      (node (ref "V32") (pin "P1") (pinfunction "N_P1") (pintype "bidirectional"))
      (node (ref "V33") (pin "P1") (pinfunction "N_P1") (pintype "bidirectional"))
      (node (ref "V34") (pin "P1") (pinfunction "N_P1") (pintype "bidirectional"))
      (node (ref "V36") (pin "P1") (pinfunction "N_P1") (pintype "bidirectional"))
      (node (ref "V6") (pin "P1") (pinfunction "N_P1") (pintype "bidirectional"))
    )
    (net (code "29") (name "Net-(C11-Pad1)") (class "Default")
      (node (ref "C11") (pin "1") (pinfunction "1_1") (pintype "passive"))
      (node (ref "U4") (pin "21") (pinfunction "DVDD_21") (pintype "bidirectional"))
      (node (ref "U4") (pin "22") (pinfunction "DVDD_22") (pintype "bidirectional"))
    )
    (net (code "30") (name "Net-(R4A-1)") (class "Default")
      (node (ref "D1") (pin "A1") (pinfunction "A1_A1") (pintype "passive"))
      (node (ref "R4") (pin "4") (pinfunction "1_4") (pintype "passive"))
    )
    (net (code "31") (name "Net-(R4A-2)") (class "Default")
      (node (ref "R4") (pin "5") (pinfunction "2_5") (pintype "passive"))
      (node (ref "R4") (pin "6") (pinfunction "2_6") (pintype "passive"))
      (node (ref "U2") (pin "1") (pinfunction "STAT_1") (pintype "output"))
    )
    (net (code "32") (name "Net-(R4B-1)") (class "Default")
      (node (ref "D1") (pin "C2") (pinfunction "C2_C2") (pintype "passive"))
      (node (ref "R4") (pin "3") (pinfunction "1_3") (pintype "passive"))
    )
    (net (code "33") (name "Net-(R4C-2)") (class "Default")
      (node (ref "D4") (pin "C1") (pinfunction "C1_C1") (pintype "passive"))
      (node (ref "R4") (pin "7") (pinfunction "2_7") (pintype "passive"))
    )
    (net (code "34") (name "Net-(R4D-2)") (class "Default")
      (node (ref "D4") (pin "C2") (pinfunction "C2_C2") (pintype "passive"))
      (node (ref "R4") (pin "8") (pinfunction "2_8") (pintype "passive"))
    )
    (net (code "35") (name "Net-(R5A-1)") (class "Default")
      (node (ref "D5") (pin "A2") (pinfunction "A2_A2") (pintype "passive"))
      (node (ref "R5") (pin "4") (pinfunction "1_4") (pintype "passive"))
    )
    (net (code "36") (name "Net-(R5B-1)") (class "Default")
      (node (ref "D5") (pin "A1") (pinfunction "A1_A1") (pintype "passive"))
      (node (ref "R5") (pin "3") (pinfunction "1_3") (pintype "passive"))
    )
    (net (code "37") (name "Net-(R5C-2)") (class "Default")
      (node (ref "D6") (pin "C1") (pinfunction "C1_C1") (pintype "passive"))
      (node (ref "R5") (pin "7") (pinfunction "2_7") (pintype "passive"))
    )
    (net (code "38") (name "Net-(R5D-2)") (class "Default")
      (node (ref "D6") (pin "C2") (pinfunction "C2_C2") (pintype "passive"))
      (node (ref "R5") (pin "8") (pinfunction "2_8") (pintype "passive"))
    )
    (net (code "39") (name "Net-(S2-C)") (class "Default")
      (node (ref "S2") (pin "2") (pinfunction "C_2") (pintype "bidirectional"))
      (node (ref "U5") (pin "12") (pinfunction "2S_12") (pintype "bidirectional"))
      (node (ref "U5") (pin "4") (pinfunction "1S_4") (pintype "bidirectional"))
    )
    (net (code "40") (name "Net-(U2-PROG)") (class "Default")
      (node (ref "R7") (pin "1") (pinfunction "1_1") (pintype "passive"))
      (node (ref "U2") (pin "5") (pinfunction "PROG_5") (pintype "input"))
    )
    (net (code "41") (name "Net-(U4-AVDD)") (class "Default")
      (node (ref "C13") (pin "1") (pinfunction "1_1") (pintype "passive"))
      (node (ref "U4") (pin "60") (pinfunction "AVDD_60") (pintype "bidirectional"))
    )
    (net (code "42") (name "Net-(U4-PG0(DIG3))") (class "Default")
      (node (ref "D6") (pin "A2") (pinfunction "A2_A2") (pintype "passive"))
      (node (ref "U4") (pin "14") (pinfunction "PG0(DIG3)_14") (pintype "bidirectional"))
    )
    (net (code "43") (name "Net-(U4-PG1(DIG1))") (class "Default")
      (node (ref "D6") (pin "A1") (pinfunction "A1_A1") (pintype "passive"))
      (node (ref "U4") (pin "15") (pinfunction "PG1(DIG1)_15") (pintype "bidirectional"))
    )
    (net (code "44") (name "Net-(U4-XTAL1)") (class "Default")
      (node (ref "C14") (pin "1") (pinfunction "1_1") (pintype "passive"))
      (node (ref "U4") (pin "57") (pinfunction "XTAL1_57") (pintype "bidirectional"))
      (node (ref "Y1") (pin "3") (pinfunction "2_3") (pintype "passive"))
    )
    (net (code "45") (name "Net-(U4-XTAL2)") (class "Default")
      (node (ref "C15") (pin "1") (pinfunction "1_1") (pintype "passive"))
      (node (ref "U4") (pin "56") (pinfunction "XTAL2_56") (pintype "bidirectional"))
      (node (ref "Y1") (pin "1") (pinfunction "1_1") (pintype "passive"))
    )
    (net (code "46") (name "PITCH") (class "Default")
      (node (ref "J3") (pin "V") (pinfunction "V_V") (pintype "bidirectional"))
      (node (ref "J8") (pin "V") (pinfunction "V_V") (pintype "bidirectional"))
      (node (ref "U4") (pin "2") (pinfunction "PF3(ADC3/DIG4)_2") (pintype "bidirectional"))
    )
    (net (code "47") (name "RESET") (class "Default")
      (node (ref "B1") (pin "1") (pinfunction "1_1") (pintype "passive"))
      (node (ref "B1") (pin "2") (pinfunction "1_2") (pintype "passive"))
      (node (ref "C1") (pin "1") (pinfunction "1_1") (pintype "passive"))
      (node (ref "J4") (pin "5") (pinfunction "5_5") (pintype "passive"))
      (node (ref "R2") (pin "1") (pinfunction "1_1") (pintype "passive"))
      (node (ref "U4") (pin "12") (pinfunction "RSTN_12") (pintype "bidirectional"))
    )
    (net (code "48") (name "RF") (class "Default")
      (node (ref "D4") (pin "A1") (pinfunction "A1_A1") (pintype "passive"))
      (node (ref "U4") (pin "16") (pinfunction "PG2(AMR)_16") (pintype "bidirectional"))
    )
    (net (code "49") (name "ROLL") (class "Default")
      (node (ref "J3") (pin "H") (pinfunction "H_H") (pintype "bidirectional"))
      (node (ref "J8") (pin "H") (pinfunction "H_H") (pintype "bidirectional"))
      (node (ref "U4") (pin "1") (pinfunction "PF2(ADC2/DIG2)_1") (pintype "bidirectional"))
    )
    (net (code "50") (name "RXI") (class "Default")
      (node (ref "U3") (pin "5") (pinfunction "RXD_5") (pintype "input"))
      (node (ref "U5") (pin "10") (pinfunction "3Z_10") (pintype "bidirectional"))
    )
    (net (code "51") (name "RXI-0") (class "Default")
      (node (ref "U4") (pin "47") (pinfunction "PE1(TXD0)_47") (pintype "bidirectional"))
      (node (ref "U5") (pin "11") (pinfunction "3Y0_11") (pintype "bidirectional"))
    )
    (net (code "52") (name "RXI-1") (class "Default")
      (node (ref "JP1") (pin "CTS") (pinfunction "2_CTS") (pintype "passive"))
      (node (ref "U5") (pin "9") (pinfunction "3Y1_9") (pintype "bidirectional"))
    )
    (net (code "53") (name "RXLED") (class "Default")
      (node (ref "D5") (pin "C2") (pinfunction "C2_C2") (pintype "passive"))
      (node (ref "U3") (pin "22") (pinfunction "RXLED_22") (pintype "input"))
    )
    (net (code "54") (name "SCK") (class "Default")
      (node (ref "J4") (pin "3") (pinfunction "3_3") (pintype "passive"))
      (node (ref "U4") (pin "37") (pinfunction "PB1(SCK/PCINT1)_37") (pintype "bidirectional"))
    )
    (net (code "55") (name "SHIELD") (class "Default")
      (node (ref "B12") (pin "P2") (pinfunction "P2_P2") (pintype "bidirectional"))
    )
    (net (code "56") (name "THROTTLE") (class "Default")
      (node (ref "J2") (pin "V") (pinfunction "V_V") (pintype "bidirectional"))
      (node (ref "J7") (pin "V") (pinfunction "V_V") (pintype "bidirectional"))
      (node (ref "U4") (pin "64") (pinfunction "PF1(ADC1)_64") (pintype "bidirectional"))
    )
    (net (code "57") (name "TXLED") (class "Default")
      (node (ref "D5") (pin "C1") (pinfunction "C1_C1") (pintype "passive"))
      (node (ref "U3") (pin "23") (pinfunction "TXLED_23") (pintype "input"))
    )
    (net (code "58") (name "TXO") (class "Default")
      (node (ref "U3") (pin "1") (pinfunction "TXD_1") (pintype "output"))
      (node (ref "U5") (pin "6") (pinfunction "2Z_6") (pintype "bidirectional"))
    )
    (net (code "59") (name "TXO-0") (class "Default")
      (node (ref "U4") (pin "46") (pinfunction "PE0(RXD0/PCINT8)_46") (pintype "bidirectional"))
      (node (ref "U5") (pin "7") (pinfunction "2Y0_7") (pintype "bidirectional"))
    )
    (net (code "60") (name "TXO-1") (class "Default")
      (node (ref "JP1") (pin "VCC") (pinfunction "3_VCC") (pintype "passive"))
      (node (ref "U5") (pin "5") (pinfunction "2Y1_5") (pintype "bidirectional"))
    )
    (net (code "61") (name "USB_D_N") (class "Default")
      (node (ref "J1") (pin "2") (pinfunction "2-D-_2") (pintype "bidirectional"))
      (node (ref "U3") (pin "16") (pinfunction "USBDM_16") (pintype "bidirectional"))
    )
    (net (code "62") (name "USB_D_P") (class "Default")
      (node (ref "J1") (pin "3") (pinfunction "3-D+_3") (pintype "bidirectional"))
      (node (ref "U3") (pin "15") (pinfunction "USBDP_15") (pintype "bidirectional"))
    )
    (net (code "63") (name "VBAT") (class "Default")
      (node (ref "D2") (pin "C") (pinfunction "C_C") (pintype "passive"))
      (node (ref "D3") (pin "C") (pinfunction "C_C") (pintype "passive"))
      (node (ref "P2") (pin "T") (pinfunction "T_T") (pintype "bidirectional"))
      (node (ref "S1") (pin "2") (pinfunction "C_2") (pintype "bidirectional"))
    )
    (net (code "64") (name "VBUS") (class "Default")
      (node (ref "C5") (pin "1") (pinfunction "1_1") (pintype "passive"))
      (node (ref "D1") (pin "A2") (pinfunction "A2_A2") (pintype "passive"))
      (node (ref "D2") (pin "A") (pinfunction "A_A") (pintype "passive"))
      (node (ref "J1") (pin "1") (pinfunction "1-VCC_1") (pintype "bidirectional"))
      (node (ref "P1") (pin "T") (pinfunction "T_T") (pintype "bidirectional"))
      (node (ref "U2") (pin "4") (pinfunction "VDD_4") (pintype "power_in"))
      (node (ref "V1") (pin "P1") (pinfunction "N_P1") (pintype "bidirectional"))
      (node (ref "V2") (pin "P1") (pinfunction "N_P1") (pintype "bidirectional"))
      (node (ref "V23") (pin "P1") (pinfunction "N_P1") (pintype "bidirectional"))
      (node (ref "V24") (pin "P1") (pinfunction "N_P1") (pintype "bidirectional"))
      (node (ref "V26") (pin "P1") (pinfunction "N_P1") (pintype "bidirectional"))
      (node (ref "V27") (pin "P1") (pinfunction "N_P1") (pintype "bidirectional"))
      (node (ref "V28") (pin "P1") (pinfunction "N_P1") (pintype "bidirectional"))
    )
    (net (code "65") (name "VREG_IN") (class "Default")
      (node (ref "C7") (pin "1") (pinfunction "1_1") (pintype "passive"))
      (node (ref "C8") (pin "1") (pinfunction "1_1") (pintype "passive"))
      (node (ref "L1") (pin "RAW") (pinfunction "VIN_RAW") (pintype "bidirectional"))
      (node (ref "S1") (pin "1") (pinfunction "ON_1") (pintype "bidirectional"))
      (node (ref "U3") (pin "20") (pinfunction "VCC_20") (pintype "power_in"))
    )
    (net (code "66") (name "YAW") (class "Default")
      (node (ref "J2") (pin "H") (pinfunction "H_H") (pintype "bidirectional"))
      (node (ref "J7") (pin "H") (pinfunction "H_H") (pintype "bidirectional"))
      (node (ref "U4") (pin "63") (pinfunction "PF0(ADC0)_63") (pintype "bidirectional"))
    )
    (net (code "67") (name "unconnected-(J1-4-ID-Pad4)") (class "Default")
      (node (ref "J1") (pin "4") (pinfunction "4-ID_4") (pintype "bidirectional"))
    )
    (net (code "68") (name "unconnected-(L1-PadSCK)") (class "Default")
      (node (ref "L1") (pin "SCK") (pinfunction "SCK_SCK") (pintype "bidirectional"))
    )
    (net (code "69") (name "unconnected-(L1-PadSDI)") (class "Default")
      (node (ref "L1") (pin "SDI") (pinfunction "SDI_SDI") (pintype "bidirectional"))
    )
    (net (code "70") (name "unconnected-(L1-PadSDO)") (class "Default")
      (node (ref "L1") (pin "SDO") (pinfunction "SDO_SDO") (pintype "bidirectional"))
    )
    (net (code "71") (name "unconnected-(L1-Pad{slash}CS)") (class "Default")
      (node (ref "L1") (pin "/CS") (pinfunction "/CS_/CS") (pintype "bidirectional"))
    )
    (net (code "72") (name "unconnected-(L1-SCL-PadCL)") (class "Default")
      (node (ref "L1") (pin "CL") (pinfunction "SCL_CL") (pintype "bidirectional"))
    )
    (net (code "73") (name "unconnected-(L1-SDA-PadDA)") (class "Default")
      (node (ref "L1") (pin "DA") (pinfunction "SDA_DA") (pintype "bidirectional"))
    )
    (net (code "74") (name "unconnected-(S1-OFF-Pad3)") (class "Default")
      (node (ref "S1") (pin "3") (pinfunction "OFF_3") (pintype "bidirectional"))
    )
    (net (code "75") (name "unconnected-(U3-DCD-Pad10)") (class "Default")
      (node (ref "U3") (pin "10") (pinfunction "DCD_10") (pintype "input"))
    )
    (net (code "76") (name "unconnected-(U3-DSR-Pad9)") (class "Default")
      (node (ref "U3") (pin "9") (pinfunction "DSR_9") (pintype "input"))
    )
    (net (code "77") (name "unconnected-(U3-OSCI-Pad27)") (class "Default")
      (node (ref "U3") (pin "27") (pinfunction "OSCI_27") (pintype "input"))
    )
    (net (code "78") (name "unconnected-(U3-OSCO-Pad28)") (class "Default")
      (node (ref "U3") (pin "28") (pinfunction "OSCO_28") (pintype "output"))
    )
    (net (code "79") (name "unconnected-(U3-PWREN-Pad14)") (class "Default")
      (node (ref "U3") (pin "14") (pinfunction "PWREN_14") (pintype "input"))
    )
    (net (code "80") (name "unconnected-(U3-RESET-Pad19)") (class "Default")
      (node (ref "U3") (pin "19") (pinfunction "RESET_19") (pintype "input"))
    )
    (net (code "81") (name "unconnected-(U3-RI-Pad6)") (class "Default")
      (node (ref "U3") (pin "6") (pinfunction "RI_6") (pintype "input"))
    )
    (net (code "82") (name "unconnected-(U3-RTS-Pad3)") (class "Default")
      (node (ref "U3") (pin "3") (pinfunction "RTS_3") (pintype "output"))
    )
    (net (code "83") (name "unconnected-(U3-SLEEP-Pad12)") (class "Default")
      (node (ref "U3") (pin "12") (pinfunction "SLEEP_12") (pintype "input"))
    )
    (net (code "84") (name "unconnected-(U3-TXDEN-Pad13)") (class "Default")
      (node (ref "U3") (pin "13") (pinfunction "TXDEN_13") (pintype "input"))
    )
    (net (code "85") (name "unconnected-(U4-AREF-Pad62)") (class "Default")
      (node (ref "U4") (pin "62") (pinfunction "AREF_62") (pintype "bidirectional"))
    )
    (net (code "86") (name "unconnected-(U4-PB0(SSN{slash}PCINT0)-Pad36)") (class "Default")
      (node (ref "U4") (pin "36") (pinfunction "PB0(SSN/PCINT0)_36") (pintype "bidirectional"))
    )
    (net (code "87") (name "unconnected-(U4-PB6(OC1B{slash}PCINT6)-Pad42)") (class "Default")
      (node (ref "U4") (pin "42") (pinfunction "PB6(OC1B/PCINT6)_42") (pintype "bidirectional"))
    )
    (net (code "88") (name "unconnected-(U4-PB7(OC0A{slash}OC1C{slash}PCINT7)-Pad43)") (class "Default")
      (node (ref "U4") (pin "43") (pinfunction "PB7(OC0A/OC1C/PCINT7)_43") (pintype "bidirectional"))
    )
    (net (code "89") (name "unconnected-(U4-PD4(ICP1)-Pad29)") (class "Default")
      (node (ref "U4") (pin "29") (pinfunction "PD4(ICP1)_29") (pintype "bidirectional"))
    )
    (net (code "90") (name "unconnected-(U4-PD5(XCK1)-Pad30)") (class "Default")
      (node (ref "U4") (pin "30") (pinfunction "PD5(XCK1)_30") (pintype "bidirectional"))
    )
    (net (code "91") (name "unconnected-(U4-PE2(XCK0{slash}AIN0)-Pad48)") (class "Default")
      (node (ref "U4") (pin "48") (pinfunction "PE2(XCK0/AIN0)_48") (pintype "bidirectional"))
    )
    (net (code "92") (name "unconnected-(U4-PE3(OC3A{slash}AIN1)-Pad49)") (class "Default")
      (node (ref "U4") (pin "49") (pinfunction "PE3(OC3A/AIN1)_49") (pintype "bidirectional"))
    )
    (net (code "93") (name "unconnected-(U4-PF4(ADC4{slash}TCK)-Pad3)") (class "Default")
      (node (ref "U4") (pin "3") (pinfunction "PF4(ADC4/TCK)_3") (pintype "bidirectional"))
    )
    (net (code "94") (name "unconnected-(U4-PF5(ADC5{slash}TMS)-Pad4)") (class "Default")
      (node (ref "U4") (pin "4") (pinfunction "PF5(ADC5/TMS)_4") (pintype "bidirectional"))
    )
    (net (code "95") (name "unconnected-(U4-PF6(ADC6{slash}TDO)-Pad5)") (class "Default")
      (node (ref "U4") (pin "5") (pinfunction "PF6(ADC6/TDO)_5") (pintype "bidirectional"))
    )
    (net (code "96") (name "unconnected-(U4-PF7(ADC7{slash}TDI)-Pad6)") (class "Default")
      (node (ref "U4") (pin "6") (pinfunction "PF7(ADC7/TDI)_6") (pintype "bidirectional"))
    )
    (net (code "97") (name "unconnected-(U4-PG3(TOSC2)-Pad17)") (class "Default")
      (node (ref "U4") (pin "17") (pinfunction "PG3(TOSC2)_17") (pintype "bidirectional"))
    )
    (net (code "98") (name "unconnected-(U4-PG4(TOSC1)-Pad18)") (class "Default")
      (node (ref "U4") (pin "18") (pinfunction "PG4(TOSC1)_18") (pintype "bidirectional"))
    )
    (net (code "99") (name "unconnected-(U4-PG5(OC0B)-Pad19)") (class "Default")
      (node (ref "U4") (pin "19") (pinfunction "PG5(OC0B)_19") (pintype "bidirectional"))
    )
    (net (code "100") (name "unconnected-(U4-RSTON-Pad13)") (class "Default")
      (node (ref "U4") (pin "13") (pinfunction "RSTON_13") (pintype "bidirectional"))
    )
  )
)
